# Todesstern.net
KiCad netlist of a schematic drawn in EasyEDA
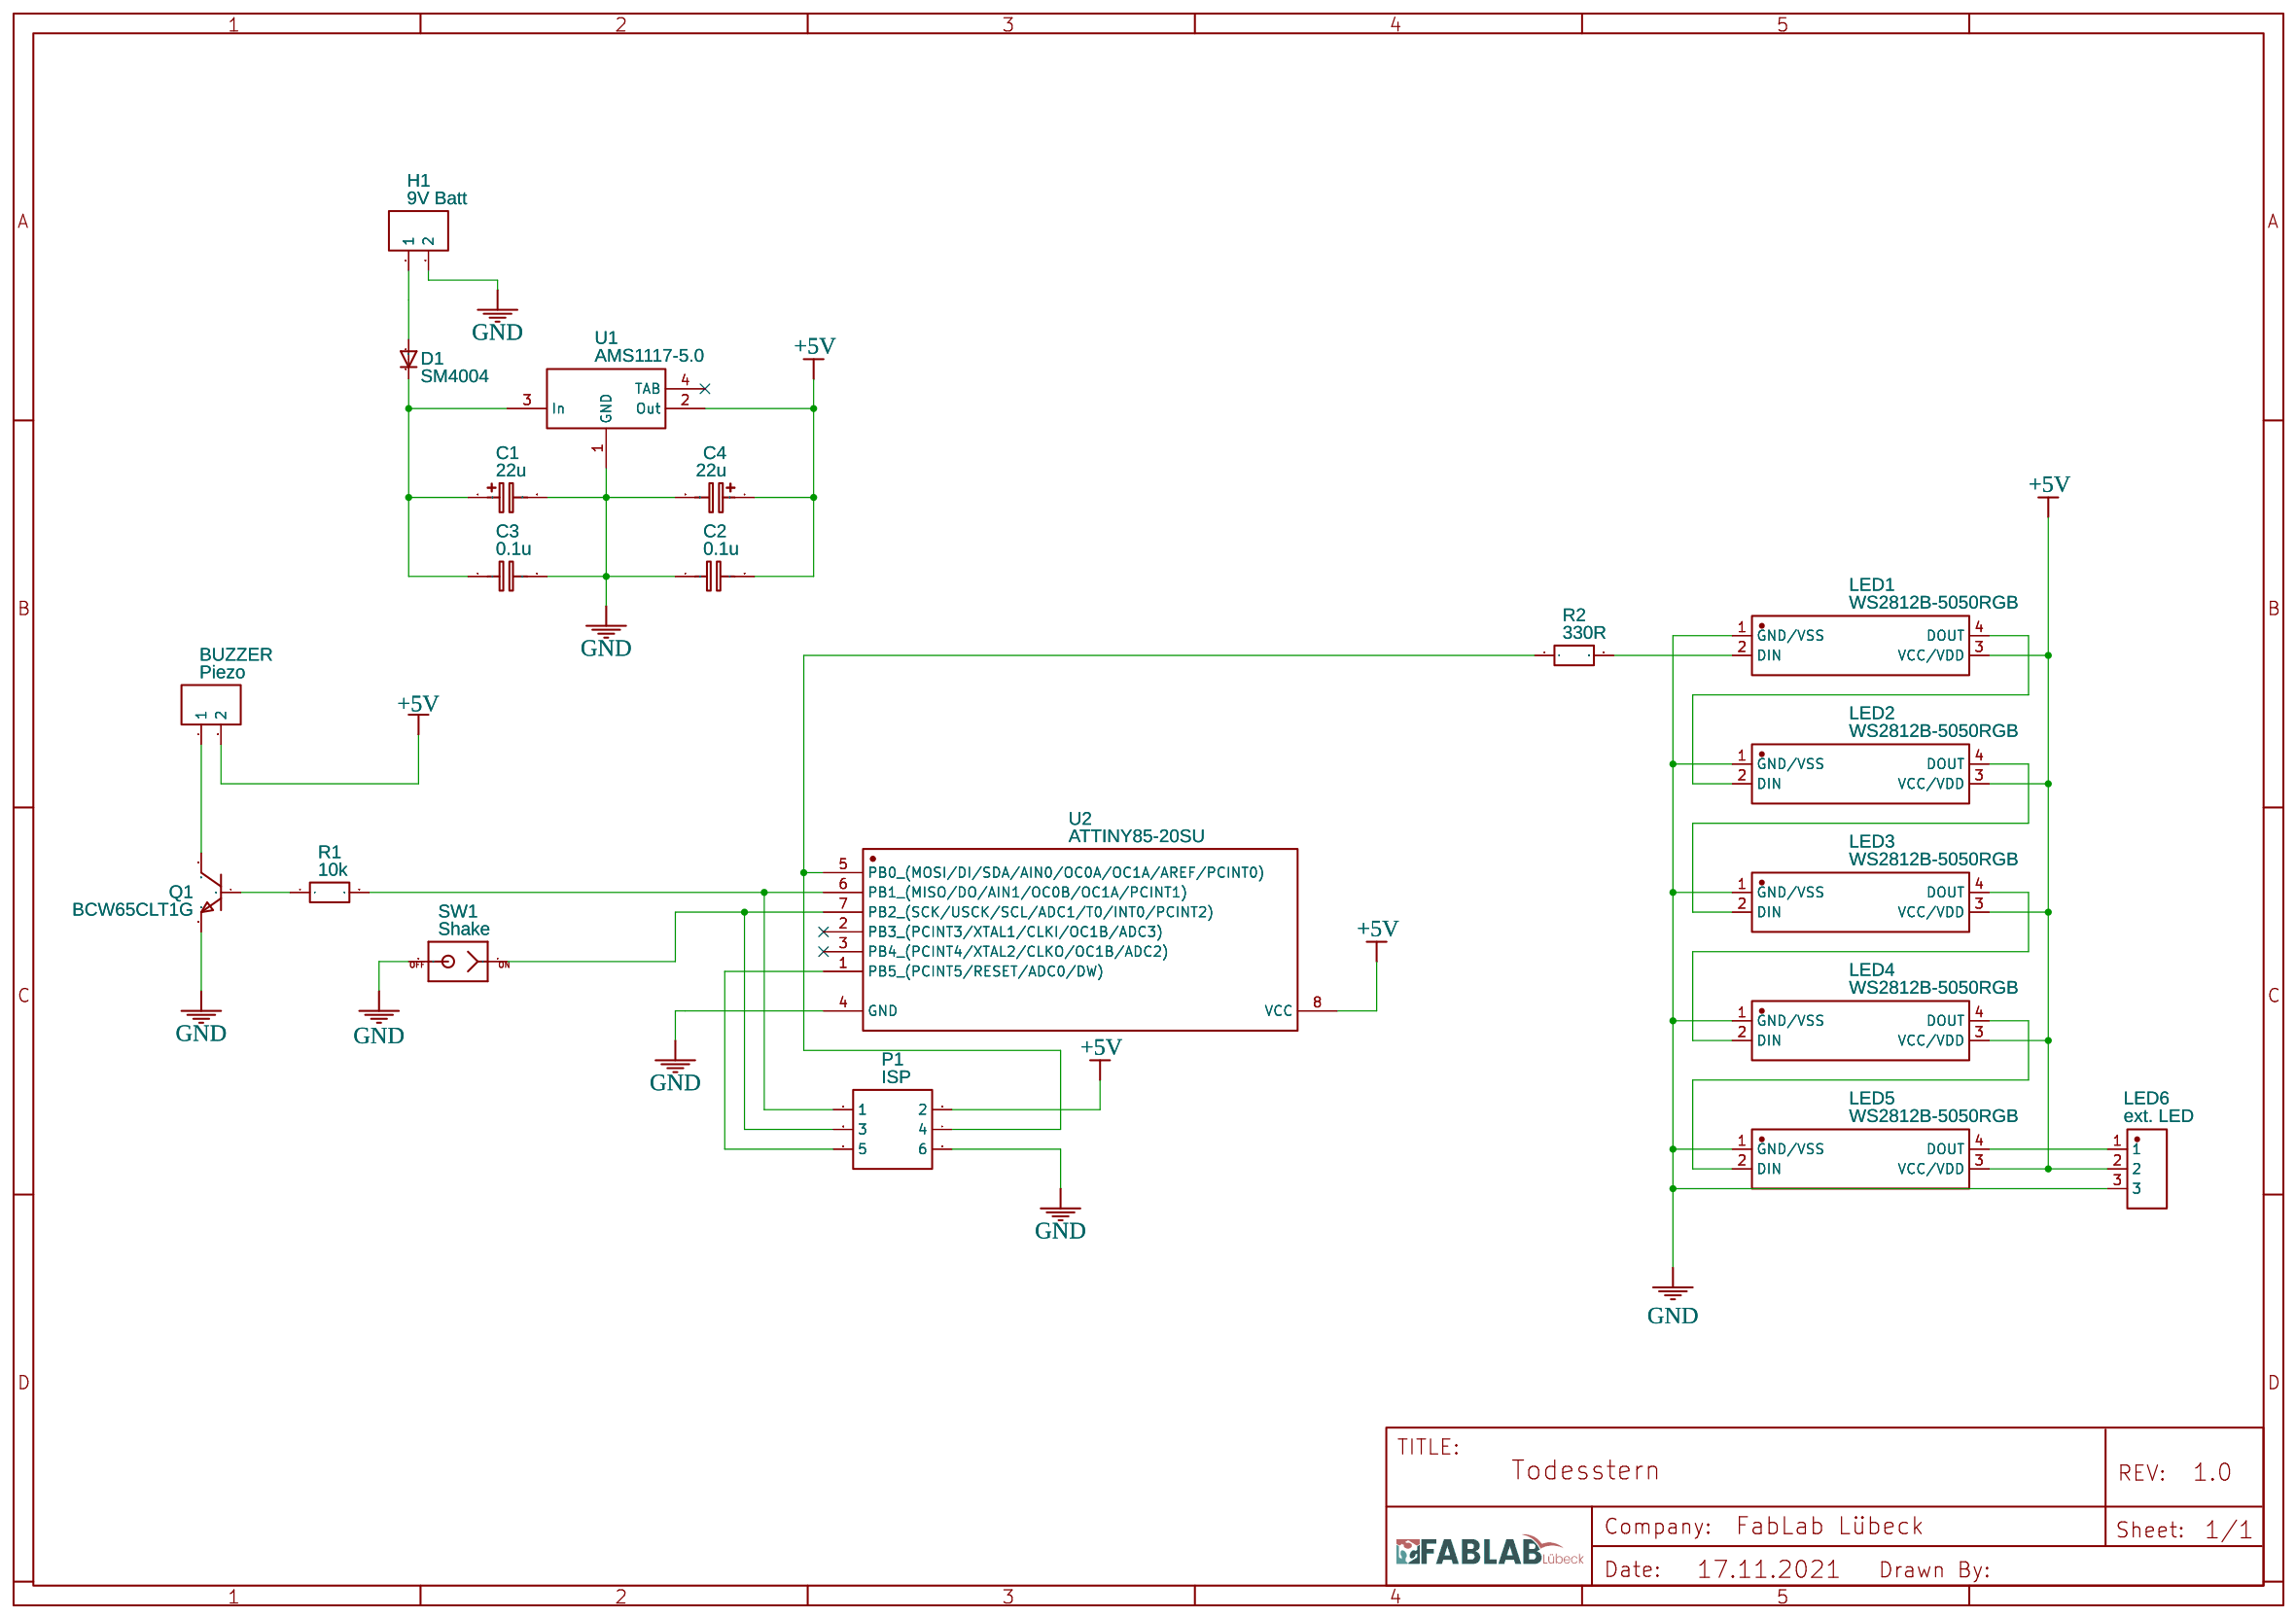
[diagram p0: schematic sheet]

(export (version "E")
  (design (tool "Eeschema 10.0.6"))
  (components
    (comp (ref "BUZZER")
      (value "Piezo")
      (fields (field (name "BOM_Supplier Part") "C49661"))
      (libsource (lib "") (part "HDR-F-2.54_1x2"))
    )
    (comp (ref "C1") (value "22u") (libsource (lib "") (part "C_Tan_SMD_C_EU")))
    (comp (ref "C2") (value "0.1u") (libsource (lib "") (part "C_0805_EU")))
    (comp (ref "C3") (value "0.1u") (libsource (lib "") (part "C_0805_EU")))
    (comp (ref "C4") (value "22u") (libsource (lib "") (part "C_Tan_SMD_C_EU_1")))
    (comp (ref "D1") (value "SM4004") (libsource (lib "") (part "SM4004")))
    (comp (ref "H1")
      (value "9V Batt")
      (fields (field (name "BOM_Supplier Part") "C49661"))
      (libsource (lib "") (part "HDR-F-2.54_1x2_1"))
    )
    (comp (ref "LED1")
      (value "WS2812B-5050RGB")
      (fields (field (name "BOM_Supplier Part") "C2838584"))
      (libsource (lib "") (part "WS2812B-5050RGB"))
    )
    (comp (ref "LED2")
      (value "WS2812B-5050RGB")
      (fields (field (name "BOM_Supplier Part") "C2838584"))
      (libsource (lib "") (part "WS2812B-5050RGB"))
    )
    (comp (ref "LED3")
      (value "WS2812B-5050RGB")
      (fields (field (name "BOM_Supplier Part") "C2838584"))
      (libsource (lib "") (part "WS2812B-5050RGB"))
    )
    (comp (ref "LED4")
      (value "WS2812B-5050RGB")
      (fields (field (name "BOM_Supplier Part") "C2838584"))
      (libsource (lib "") (part "WS2812B-5050RGB"))
    )
    (comp (ref "LED5")
      (value "WS2812B-5050RGB")
      (fields (field (name "BOM_Supplier Part") "C2838584"))
      (libsource (lib "") (part "WS2812B-5050RGB"))
    )
    (comp (ref "LED6")
      (value "ext. LED")
      (fields
        (field (name "BOM_Manufacturer Part") "PZ200-1-03-Z")
        (field (name "BOM_Supplier Part") "C2905949")
      )
      (libsource (lib "") (part "PZ200-1-03-Z"))
    )
    (comp (ref "P1")
      (value "ISP")
      (fields
        (field (name "BOM_Manufacturer Part") "2X3 2.54mm IDC Box")
        (field (name "BOM_Supplier Part") "C11214")
      )
      (libsource (lib "") (part "HDR-IDC-2.54-2X3P"))
    )
    (comp (ref "Q1")
      (value "BCW65CLT1G")
      (fields (field (name "BOM_Supplier Part") "C232540"))
      (libsource (lib "") (part "BCW65CLT1G"))
    )
    (comp (ref "R1") (value "10k") (libsource (lib "") (part "R_0805_EU")))
    (comp (ref "R2") (value "330R") (libsource (lib "") (part "R_0805_EU")))
    (comp (ref "SW1")
      (value "Shake")
      (fields (field (name "BOM_Manufacturer Part") "SW-200D"))
      (libsource (lib "") (part "SW-200D"))
    )
    (comp (ref "U1")
      (value "AMS1117-5.0")
      (fields (field (name "BOM_Supplier Part") "C6187"))
      (libsource (lib "") (part "AMS1117-5.0"))
    )
    (comp (ref "U2")
      (value "ATTINY85-20SU")
      (fields (field (name "BOM_Supplier Part") "C89852"))
      (libsource (lib "") (part "ATTINY85-20SU"))
    )
  )
  (nets
    (net (code "1") (name "+5V") (class "Default")
      (node (ref "BUZZER") (pin "2") (pinfunction "2_2") (pintype "input"))
      (node (ref "C2") (pin "2") (pinfunction "2_2") (pintype "unspecified"))
      (node (ref "C4") (pin "1") (pinfunction "1_1") (pintype "unspecified"))
      (node (ref "LED1") (pin "3") (pinfunction "VCC/VDD_3") (pintype "unspecified"))
      (node (ref "LED2") (pin "3") (pinfunction "VCC/VDD_3") (pintype "unspecified"))
      (node (ref "LED3") (pin "3") (pinfunction "VCC/VDD_3") (pintype "unspecified"))
      (node (ref "LED4") (pin "3") (pinfunction "VCC/VDD_3") (pintype "unspecified"))
      (node (ref "LED5") (pin "3") (pinfunction "VCC/VDD_3") (pintype "unspecified"))
      (node (ref "LED6") (pin "2") (pinfunction "2_2") (pintype "unspecified"))
      (node (ref "P1") (pin "2") (pinfunction "2_2") (pintype "unspecified"))
      (node (ref "U1") (pin "2") (pinfunction "Out_2") (pintype "unspecified"))
      (node (ref "U2") (pin "8") (pinfunction "VCC_8") (pintype "passive"))
    )
    (net (code "2") (name "GND") (class "Default")
      (node (ref "C1") (pin "2") (pinfunction "2_2") (pintype "unspecified"))
      (node (ref "C2") (pin "1") (pinfunction "1_1") (pintype "unspecified"))
      (node (ref "C3") (pin "2") (pinfunction "2_2") (pintype "unspecified"))
      (node (ref "C4") (pin "2") (pinfunction "2_2") (pintype "unspecified"))
      (node (ref "H1") (pin "2") (pinfunction "2_2") (pintype "input"))
      (node (ref "LED1") (pin "1") (pinfunction "GND/VSS_1") (pintype "unspecified"))
      (node (ref "LED2") (pin "1") (pinfunction "GND/VSS_1") (pintype "unspecified"))
      (node (ref "LED3") (pin "1") (pinfunction "GND/VSS_1") (pintype "unspecified"))
      (node (ref "LED4") (pin "1") (pinfunction "GND/VSS_1") (pintype "unspecified"))
      (node (ref "LED5") (pin "1") (pinfunction "GND/VSS_1") (pintype "unspecified"))
      (node (ref "LED6") (pin "3") (pinfunction "3_3") (pintype "unspecified"))
      (node (ref "P1") (pin "6") (pinfunction "6_6") (pintype "unspecified"))
      (node (ref "Q1") (pin "2") (pinfunction "E_2") (pintype "unspecified"))
      (node (ref "SW1") (pin "2") (pinfunction "2_2") (pintype "unspecified"))
      (node (ref "U1") (pin "1") (pinfunction "GND_1") (pintype "unspecified"))
      (node (ref "U2") (pin "4") (pinfunction "GND_4") (pintype "passive"))
    )
    (net (code "3") (name "Net-(D1-PadA)") (class "Default")
      (node (ref "D1") (pin "A") (pinfunction "A_A") (pintype "unspecified"))
      (node (ref "H1") (pin "1") (pinfunction "1_1") (pintype "input"))
    )
    (net (code "4") (name "Net-(LED1-DIN)") (class "Default")
      (node (ref "LED1") (pin "2") (pinfunction "DIN_2") (pintype "unspecified"))
      (node (ref "R2") (pin "2") (pinfunction "2_2") (pintype "unspecified"))
    )
    (net (code "5") (name "Net-(LED1-DOUT)") (class "Default")
      (node (ref "LED1") (pin "4") (pinfunction "DOUT_4") (pintype "unspecified"))
      (node (ref "LED2") (pin "2") (pinfunction "DIN_2") (pintype "unspecified"))
    )
    (net (code "6") (name "Net-(LED2-DOUT)") (class "Default")
      (node (ref "LED2") (pin "4") (pinfunction "DOUT_4") (pintype "unspecified"))
      (node (ref "LED3") (pin "2") (pinfunction "DIN_2") (pintype "unspecified"))
    )
    (net (code "7") (name "Net-(LED3-DOUT)") (class "Default")
      (node (ref "LED3") (pin "4") (pinfunction "DOUT_4") (pintype "unspecified"))
      (node (ref "LED4") (pin "2") (pinfunction "DIN_2") (pintype "unspecified"))
    )
    (net (code "8") (name "Net-(LED4-DOUT)") (class "Default")
      (node (ref "LED4") (pin "4") (pinfunction "DOUT_4") (pintype "unspecified"))
      (node (ref "LED5") (pin "2") (pinfunction "DIN_2") (pintype "unspecified"))
    )
    (net (code "9") (name "Net-(LED5-DOUT)") (class "Default")
      (node (ref "LED5") (pin "4") (pinfunction "DOUT_4") (pintype "unspecified"))
      (node (ref "LED6") (pin "1") (pinfunction "1_1") (pintype "unspecified"))
    )
    (net (code "10") (name "Net-(Q1-B)") (class "Default")
      (node (ref "Q1") (pin "1") (pinfunction "B_1") (pintype "unspecified"))
      (node (ref "R1") (pin "1") (pinfunction "1_1") (pintype "unspecified"))
    )
    (net (code "11") (name "Net-(Q1-C)") (class "Default")
      (node (ref "BUZZER") (pin "1") (pinfunction "1_1") (pintype "input"))
      (node (ref "Q1") (pin "3") (pinfunction "C_3") (pintype "unspecified"))
    )
    (net (code "12") (name "Net-(U1-In)") (class "Default")
      (node (ref "C1") (pin "1") (pinfunction "1_1") (pintype "unspecified"))
      (node (ref "C3") (pin "1") (pinfunction "1_1") (pintype "unspecified"))
      (node (ref "D1") (pin "C") (pinfunction "C_C") (pintype "unspecified"))
      (node (ref "U1") (pin "3") (pinfunction "In_3") (pintype "unspecified"))
    )
    (net (code "13") (name "Net-(U2-PB0_(MOSI{slash}DI{slash}SDA{slash}AIN0{slash}OC0A{slash}OC1A{slash}AREF{slash}PCINT0))") (class "Default")
      (node (ref "P1") (pin "4") (pinfunction "4_4") (pintype "unspecified"))
      (node (ref "R2") (pin "1") (pinfunction "1_1") (pintype "unspecified"))
      (node (ref "U2") (pin "5") (pinfunction "PB0_(MOSI/DI/SDA/AIN0/OC0A/OC1A/AREF/PCINT0)_5") (pintype "bidirectional"))
    )
    (net (code "14") (name "Net-(U2-PB1_(MISO{slash}DO{slash}AIN1{slash}OC0B{slash}OC1A{slash}PCINT1))") (class "Default")
      (node (ref "P1") (pin "1") (pinfunction "1_1") (pintype "unspecified"))
      (node (ref "R1") (pin "2") (pinfunction "2_2") (pintype "unspecified"))
      (node (ref "U2") (pin "6") (pinfunction "PB1_(MISO/DO/AIN1/OC0B/OC1A/PCINT1)_6") (pintype "bidirectional"))
    )
    (net (code "15") (name "Net-(U2-PB2_(SCK{slash}USCK{slash}SCL{slash}ADC1{slash}T0{slash}INT0{slash}PCINT2))") (class "Default")
      (node (ref "P1") (pin "3") (pinfunction "3_3") (pintype "unspecified"))
      (node (ref "SW1") (pin "1") (pinfunction "1_1") (pintype "unspecified"))
      (node (ref "U2") (pin "7") (pinfunction "PB2_(SCK/USCK/SCL/ADC1/T0/INT0/PCINT2)_7") (pintype "bidirectional"))
    )
    (net (code "16") (name "Net-(U2-PB5_(PCINT5{slash}RESET{slash}ADC0{slash}DW))") (class "Default")
      (node (ref "P1") (pin "5") (pinfunction "5_5") (pintype "unspecified"))
      (node (ref "U2") (pin "1") (pinfunction "PB5_(PCINT5/RESET/ADC0/DW)_1") (pintype "bidirectional"))
    )
    (net (code "17") (name "unconnected-(U1-TAB-Pad4)") (class "Default")
      (node (ref "U1") (pin "4") (pinfunction "TAB_4") (pintype "unspecified+no_connect"))
    )
    (net (code "18") (name "unconnected-(U2-PB3_(PCINT3{slash}XTAL1{slash}CLKI{slash}OC1B{slash}ADC3)-Pad2)") (class "Default")
      (node (ref "U2") (pin "2") (pinfunction "PB3_(PCINT3/XTAL1/CLKI/OC1B/ADC3)_2") (pintype "bidirectional+no_connect"))
    )
    (net (code "19") (name "unconnected-(U2-PB4_(PCINT4{slash}XTAL2{slash}CLKO{slash}OC1B{slash}ADC2)-Pad3)") (class "Default")
      (node (ref "U2") (pin "3") (pinfunction "PB4_(PCINT4/XTAL2/CLKO/OC1B/ADC2)_3") (pintype "bidirectional+no_connect"))
    )
  )
)
